# PDB.net
KiCad netlist of a schematic drawn in Altium Designer
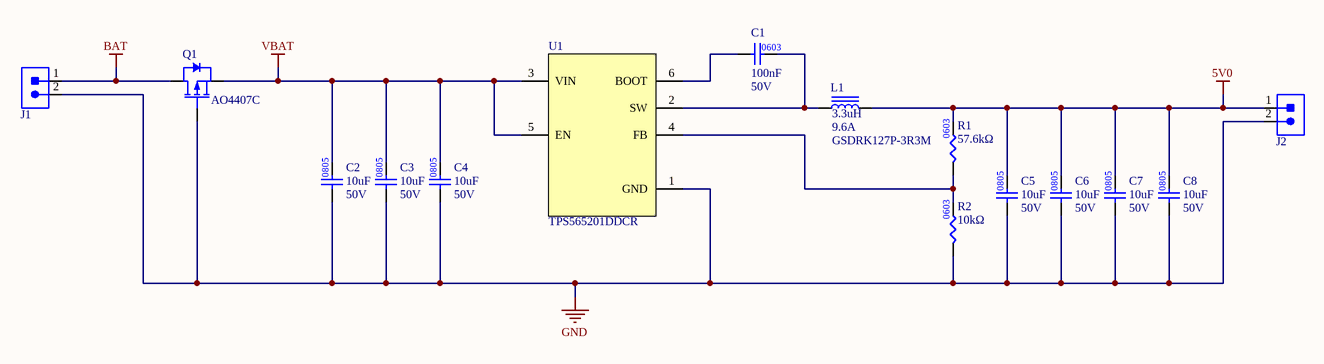
[diagram p0: PDB.SchDoc]

(export (version "E")
  (design (tool "Eeschema 10.0.6"))
  (components
    (comp (ref "C1")
      (value "100nF")
      (footprint "CAP0603")
      (description "CAP CER 100NF 50V X7R 0603")
      (fields
        (field (name "TOLERANCE") "10%")
        (field (name "VOLTAGE") "50V")
        (field (name "Comment") "CAP_100nF_50V_0603")
      )
      (libsource (lib "PDB") (part "CAP_100nF_50V_0603"))
    )
    (comp (ref "C2")
      (value "10uF")
      (footprint "CAP0805")
      (description "CAP CER 10UF 50V X5R 0805")
      (fields
        (field (name "TOLERANCE") "10%")
        (field (name "VOLTAGE") "50V")
        (field (name "Comment") "CAP_10uF_50V_0805")
      )
      (libsource (lib "PDB") (part "CAP_10uF_50V_0805"))
    )
    (comp (ref "C3")
      (value "10uF")
      (footprint "CAP0805")
      (description "CAP CER 10UF 50V X5R 0805")
      (fields
        (field (name "TOLERANCE") "10%")
        (field (name "VOLTAGE") "50V")
        (field (name "Comment") "CAP_10uF_50V_0805")
      )
      (libsource (lib "PDB") (part "CAP_10uF_50V_0805"))
    )
    (comp (ref "C4")
      (value "10uF")
      (footprint "CAP0805")
      (description "CAP CER 10UF 50V X5R 0805")
      (fields
        (field (name "TOLERANCE") "10%")
        (field (name "VOLTAGE") "50V")
        (field (name "Comment") "CAP_10uF_50V_0805")
      )
      (libsource (lib "PDB") (part "CAP_10uF_50V_0805"))
    )
    (comp (ref "C5")
      (value "10uF")
      (footprint "CAP0805")
      (description "CAP CER 10UF 50V X5R 0805")
      (fields
        (field (name "TOLERANCE") "10%")
        (field (name "VOLTAGE") "50V")
        (field (name "Comment") "CAP_10uF_50V_0805")
      )
      (libsource (lib "PDB") (part "CAP_10uF_50V_0805"))
    )
    (comp (ref "C6")
      (value "10uF")
      (footprint "CAP0805")
      (description "CAP CER 10UF 50V X5R 0805")
      (fields
        (field (name "TOLERANCE") "10%")
        (field (name "VOLTAGE") "50V")
        (field (name "Comment") "CAP_10uF_50V_0805")
      )
      (libsource (lib "PDB") (part "CAP_10uF_50V_0805"))
    )
    (comp (ref "C7")
      (value "10uF")
      (footprint "CAP0805")
      (description "CAP CER 10UF 50V X5R 0805")
      (fields
        (field (name "TOLERANCE") "10%")
        (field (name "VOLTAGE") "50V")
        (field (name "Comment") "CAP_10uF_50V_0805")
      )
      (libsource (lib "PDB") (part "CAP_10uF_50V_0805"))
    )
    (comp (ref "C8")
      (value "10uF")
      (footprint "CAP0805")
      (description "CAP CER 10UF 50V X5R 0805")
      (fields
        (field (name "TOLERANCE") "10%")
        (field (name "VOLTAGE") "50V")
        (field (name "Comment") "CAP_10uF_50V_0805")
      )
      (libsource (lib "PDB") (part "CAP_10uF_50V_0805"))
    )
    (comp (ref "J1")
      (value "CON_2POS_SCREW_TERM")
      (footprint "1935161")
      (description "TERM BLK 2POS SIDE ENTRY 5MM")
      (libsource (lib "") (part "CON_2POS_SCREW_TERM_1"))
    )
    (comp (ref "J2")
      (value "CON_2POS_SCREW_TERM")
      (footprint "1935161")
      (description "TERM BLK 2POS SIDE ENTRY 5MM")
      (libsource (lib "PDB") (part "CON_2POS_SCREW_TERM"))
    )
    (comp (ref "L1")
      (value "3.3uH")
      (footprint "GSDRK127P-3R3M")
      (description "IND 3.3UH 9.6A 10M OHM 0805")
      (fields
        (field (name "TOLERANCE") "20%")
        (field (name "CURRENT RATING") "9.6A")
        (field (name "MANUFACTURER PART NUMBER 1") "GSDRK127P-3R3M")
        (field (name "Comment") "IND_3.3uH_9.6A")
      )
      (libsource (lib "PDB") (part "IND_3.3uH_9.6A"))
    )
    (comp (ref "Q1")
      (value "PMOS_30V_14A")
      (footprint "SO-8_PMOS_AO4407C")
      (description "MOSFET P-CH 30V 14A SO-8")
      (fields (field (name "MANUFACTURER PART NUMBER 1") "AO4407C"))
      (libsource (lib "PDB") (part "PMOS_30V_14A"))
    )
    (comp (ref "R1")
      (value "57.6kΩ")
      (footprint "RES0603")
      (description "RES 57.6K OHM 1% 1/10W 0603")
      (fields (field (name "TOLERANCE") "1%") (field (name "Comment") "RES_57.6kΩ_0603_1%"))
      (libsource (lib "PDB") (part "RES_57.6kΩ_0603_1%"))
    )
    (comp (ref "R2")
      (value "10kΩ")
      (footprint "RES0603")
      (description "RES 10K OHM 1% 1/10W 0603")
      (fields (field (name "TOLERANCE") "1%") (field (name "Comment") "RES_10kΩ_0603_1%"))
      (libsource (lib "PDB") (part "RES_10kΩ_0603_1%"))
    )
    (comp (ref "U1")
      (value "TPS565201DDCR")
      (footprint "TPS565201DDCR")
      (description "IC REG BUCK ADJ 5A TSOT23-6")
      (fields
        (field (name "MANUFACTURER") "Texas Instruments")
        (field (name "MANUFACTURER PART NUMBER") "TPS565201DDCR")
      )
      (libsource (lib "PDB") (part "TPS565201DDCR"))
    )
  )
  (nets
    (net (code "1") (name "5V0") (class "Default")
      (node (ref "C5") (pin "2") (pinfunction "2_2") (pintype "passive"))
      (node (ref "C6") (pin "2") (pinfunction "2_2") (pintype "passive"))
      (node (ref "C7") (pin "2") (pinfunction "2_2") (pintype "passive"))
      (node (ref "C8") (pin "2") (pinfunction "2_2") (pintype "passive"))
      (node (ref "J2") (pin "1") (pinfunction "1_1") (pintype "passive"))
      (node (ref "L1") (pin "2") (pinfunction "2_2") (pintype "passive"))
      (node (ref "R1") (pin "2") (pinfunction "2_2") (pintype "passive"))
    )
    (net (code "2") (name "BAT") (class "Default")
      (node (ref "J1") (pin "1") (pinfunction "1_1") (pintype "passive"))
      (node (ref "Q1") (pin "3") (pinfunction "Drain_3") (pintype "passive"))
    )
    (net (code "3") (name "GND") (class "Default")
      (node (ref "C2") (pin "1") (pinfunction "1_1") (pintype "passive"))
      (node (ref "C3") (pin "1") (pinfunction "1_1") (pintype "passive"))
      (node (ref "C4") (pin "1") (pinfunction "1_1") (pintype "passive"))
      (node (ref "C5") (pin "1") (pinfunction "1_1") (pintype "passive"))
      (node (ref "C6") (pin "1") (pinfunction "1_1") (pintype "passive"))
      (node (ref "C7") (pin "1") (pinfunction "1_1") (pintype "passive"))
      (node (ref "C8") (pin "1") (pinfunction "1_1") (pintype "passive"))
      (node (ref "J1") (pin "2") (pinfunction "2_2") (pintype "passive"))
      (node (ref "J2") (pin "2") (pinfunction "2_2") (pintype "passive"))
      (node (ref "Q1") (pin "2") (pinfunction "Gate_2") (pintype "passive"))
      (node (ref "R2") (pin "1") (pinfunction "1_1") (pintype "passive"))
      (node (ref "U1") (pin "1") (pinfunction "GND_1") (pintype "passive"))
    )
    (net (code "4") (name "Net-(U1-BOOT)") (class "Default")
      (node (ref "C1") (pin "1") (pinfunction "1_1") (pintype "passive"))
      (node (ref "U1") (pin "6") (pinfunction "BOOT_6") (pintype "passive"))
    )
    (net (code "5") (name "Net-(U1-FB)") (class "Default")
      (node (ref "R1") (pin "1") (pinfunction "1_1") (pintype "passive"))
      (node (ref "R2") (pin "2") (pinfunction "2_2") (pintype "passive"))
      (node (ref "U1") (pin "4") (pinfunction "FB_4") (pintype "passive"))
    )
    (net (code "6") (name "Net-(U1-SW)") (class "Default")
      (node (ref "C1") (pin "2") (pinfunction "2_2") (pintype "passive"))
      (node (ref "L1") (pin "1") (pinfunction "1_1") (pintype "passive"))
      (node (ref "U1") (pin "2") (pinfunction "SW_2") (pintype "passive"))
    )
    (net (code "7") (name "VBAT") (class "Default")
      (node (ref "C2") (pin "2") (pinfunction "2_2") (pintype "passive"))
      (node (ref "C3") (pin "2") (pinfunction "2_2") (pintype "passive"))
      (node (ref "C4") (pin "2") (pinfunction "2_2") (pintype "passive"))
      (node (ref "Q1") (pin "1") (pinfunction "Source_1") (pintype "passive"))
      (node (ref "U1") (pin "3") (pinfunction "VIN_3") (pintype "passive"))
      (node (ref "U1") (pin "5") (pinfunction "EN_5") (pintype "passive"))
    )
  )
)
